# RomeBoardV1_2.net
KiCad netlist of a schematic drawn in EAGLE
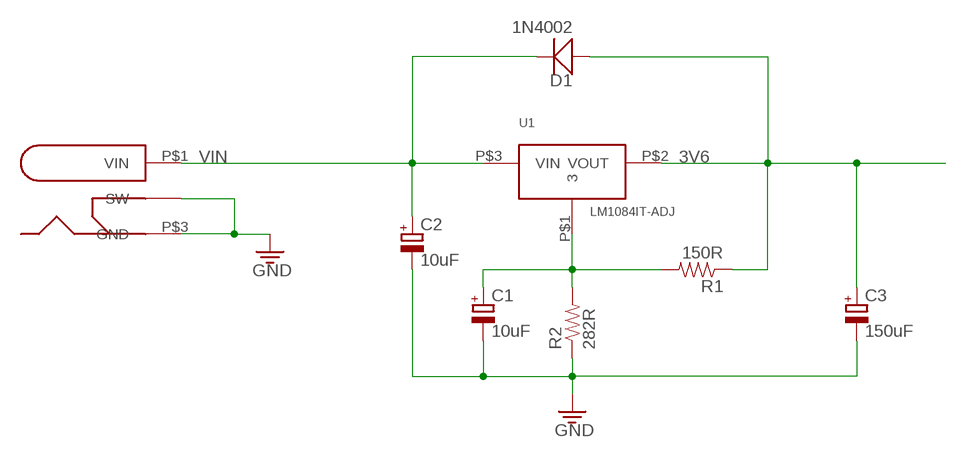
[diagram p0: schematic, sheet 1]
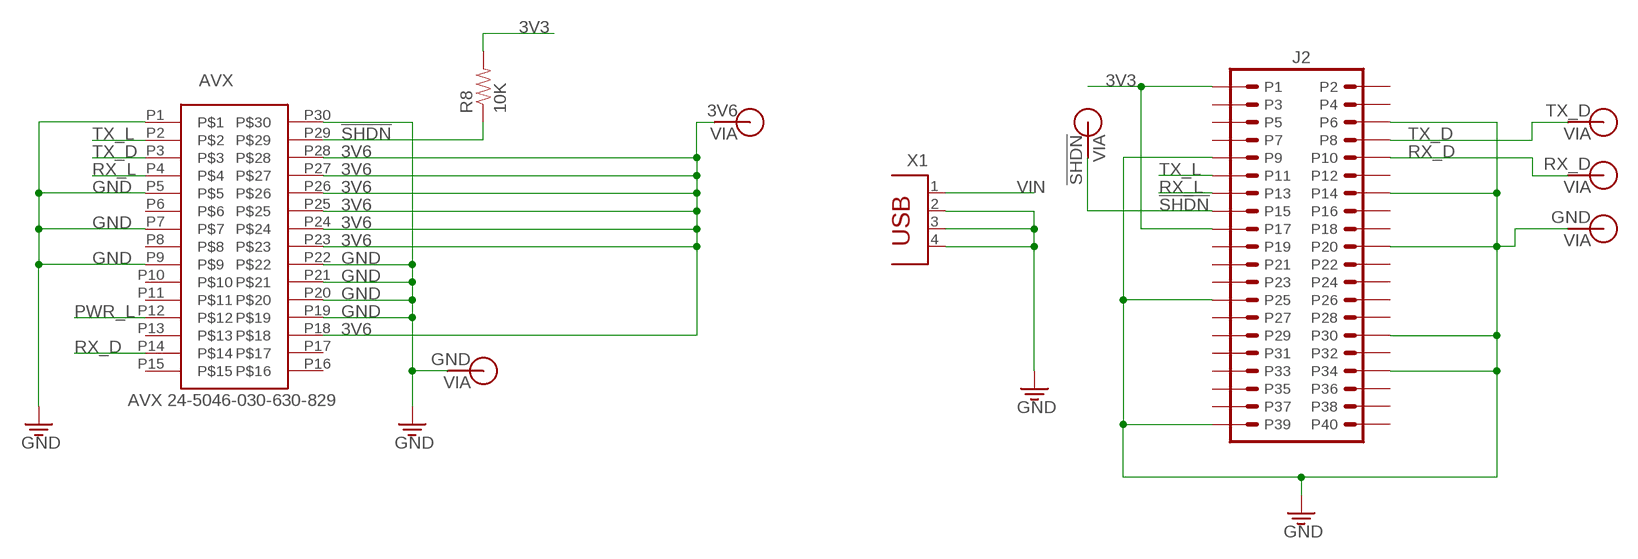
[diagram p1: schematic, sheet 2]
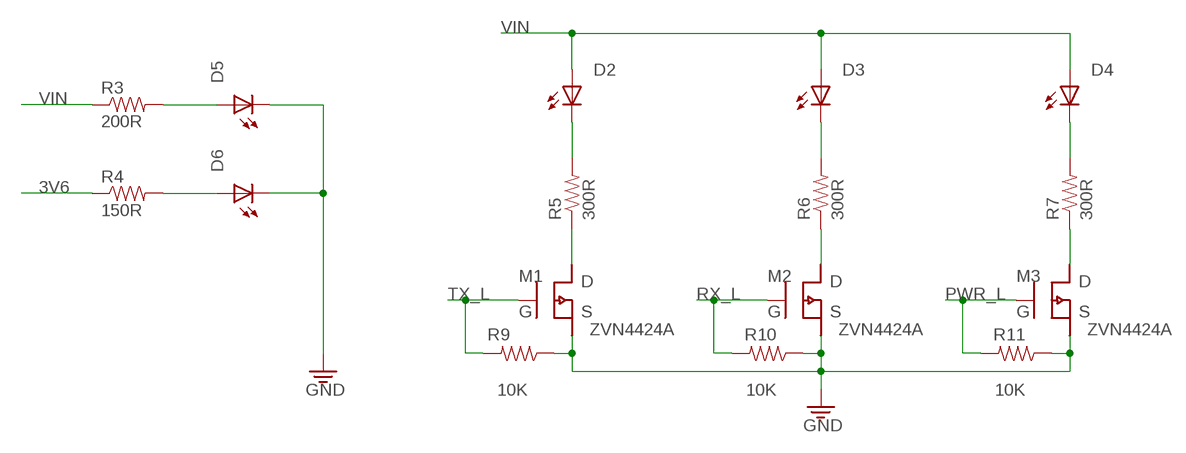
[diagram p2: schematic, sheet 3]
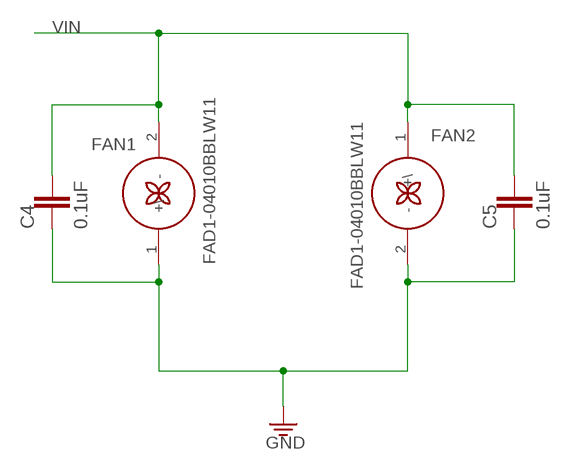
[diagram p3: schematic, sheet 4]

(export (version "E")
  (design (tool "Eeschema 10.0.6"))
  (components
    (comp (ref "C4")
      (value "0.1uF")
      (footprint "eagle-import:C050-025X075")
      (libsource (lib "eagle-import") (part "CAP5MM-THRU-HOLE"))
    )
    (comp (ref "C5")
      (value "0.1uF")
      (footprint "eagle-import:C050-025X075")
      (libsource (lib "eagle-import") (part "CAP5MM-THRU-HOLE"))
    )
    (comp (ref "FAN1")
      (value "FAD1-04010BBLW11")
      (footprint "eagle-import:1X2-POL")
      (libsource (lib "eagle-import") (part "FAD1-04010BBLW11"))
    )
    (comp (ref "FAN2")
      (value "FAD1-04010BBLW11")
      (footprint "eagle-import:1X2-POL")
      (libsource (lib "eagle-import") (part "FAD1-04010BBLW11"))
    )
    (comp (ref "AVX")
      (value "AVX-24-5046-030-630-829")
      (footprint "eagle-import:AVX-24-5046-630-829")
      (libsource (lib "eagle-import") (part "AVX-24-5046-030-630-829"))
    )
    (comp (ref "J2")
      (value "RASPBERRY-PI-HEADER")
      (footprint "eagle-import:HEADER-20X02")
      (libsource (lib "eagle-import") (part "RASPBERRY-PI-HEADER"))
    )
    (comp (ref "R8")
      (value "10K")
      (footprint "eagle-import:AXIAL-0.4")
      (libsource (lib "eagle-import") (part "RESISTOR-PTH0.4"))
    )
    (comp (ref "V1")
      (value "TX_D")
      (footprint "eagle-import:VIA-60MIL")
      (libsource (lib "eagle-import") (part "VIA-60MIL"))
    )
    (comp (ref "V2")
      (value "RX_D")
      (footprint "eagle-import:VIA-60MIL")
      (libsource (lib "eagle-import") (part "VIA-60MIL"))
    )
    (comp (ref "V3")
      (value "GND")
      (footprint "eagle-import:VIA-60MIL")
      (libsource (lib "eagle-import") (part "VIA-60MIL"))
    )
    (comp (ref "V4")
      (value "GND")
      (footprint "eagle-import:VIA-120MIL")
      (libsource (lib "eagle-import") (part "VIA-120MIL"))
    )
    (comp (ref "V5")
      (value "3V6")
      (footprint "eagle-import:VIA-120MIL")
      (libsource (lib "eagle-import") (part "VIA-120MIL"))
    )
    (comp (ref "V6")
      (value "!SHDN")
      (footprint "eagle-import:VIA-60MIL")
      (libsource (lib "eagle-import") (part "VIA-60MIL"))
    )
    (comp (ref "X1")
      (value "PN87520")
      (footprint "eagle-import:PN87520")
      (libsource (lib "eagle-import") (part "PN87520"))
    )
    (comp (ref "D2")
      (value "LEDTHRU-HOLE-CONNECTOR")
      (footprint "eagle-import:1X2-POL")
      (libsource (lib "eagle-import") (part "LEDTHRU-HOLE-CONNECTOR"))
    )
    (comp (ref "D3")
      (value "LEDTHRU-HOLE-CONNECTOR")
      (footprint "eagle-import:1X2-POL")
      (libsource (lib "eagle-import") (part "LEDTHRU-HOLE-CONNECTOR"))
    )
    (comp (ref "D4")
      (value "LEDTHRU-HOLE-CONNECTOR")
      (footprint "eagle-import:1X2-POL")
      (libsource (lib "eagle-import") (part "LEDTHRU-HOLE-CONNECTOR"))
    )
    (comp (ref "D5")
      (value "LEDTHRU-HOLE-CONNECTOR")
      (footprint "eagle-import:1X2-POL")
      (libsource (lib "eagle-import") (part "LEDTHRU-HOLE-CONNECTOR"))
    )
    (comp (ref "D6")
      (value "LEDTHRU-HOLE-CONNECTOR")
      (footprint "eagle-import:1X2-POL")
      (libsource (lib "eagle-import") (part "LEDTHRU-HOLE-CONNECTOR"))
    )
    (comp (ref "M1")
      (value "ZVN4424A")
      (footprint "eagle-import:TO-923-MOS")
      (libsource (lib "eagle-import") (part "ZVN4424A"))
    )
    (comp (ref "M2")
      (value "ZVN4424A")
      (footprint "eagle-import:TO-923-MOS")
      (libsource (lib "eagle-import") (part "ZVN4424A"))
    )
    (comp (ref "M3")
      (value "ZVN4424A")
      (footprint "eagle-import:TO-923-MOS")
      (libsource (lib "eagle-import") (part "ZVN4424A"))
    )
    (comp (ref "R3")
      (value "200R")
      (footprint "eagle-import:AXIAL-0.4")
      (libsource (lib "eagle-import") (part "RESISTOR-PTH0.4"))
    )
    (comp (ref "R4")
      (value "150R")
      (footprint "eagle-import:AXIAL-0.4")
      (libsource (lib "eagle-import") (part "RESISTOR-PTH0.4"))
    )
    (comp (ref "R5")
      (value "300R")
      (footprint "eagle-import:AXIAL-0.4")
      (libsource (lib "eagle-import") (part "RESISTOR-PTH0.4"))
    )
    (comp (ref "R6")
      (value "300R")
      (footprint "eagle-import:AXIAL-0.4")
      (libsource (lib "eagle-import") (part "RESISTOR-PTH0.4"))
    )
    (comp (ref "R7")
      (value "300R")
      (footprint "eagle-import:AXIAL-0.4")
      (libsource (lib "eagle-import") (part "RESISTOR-PTH0.4"))
    )
    (comp (ref "R9")
      (value "10K")
      (footprint "eagle-import:AXIAL-0.4")
      (libsource (lib "eagle-import") (part "RESISTOR-PTH0.4"))
    )
    (comp (ref "R10")
      (value "10K")
      (footprint "eagle-import:AXIAL-0.4")
      (libsource (lib "eagle-import") (part "RESISTOR-PTH0.4"))
    )
    (comp (ref "R11")
      (value "10K")
      (footprint "eagle-import:AXIAL-0.4")
      (libsource (lib "eagle-import") (part "RESISTOR-PTH0.4"))
    )
    (comp (ref "C1")
      (value "10uF")
      (footprint "eagle-import:E2,5-7")
      (libsource (lib "eagle-import") (part "CPOL-EUE2.5-7"))
    )
    (comp (ref "C2")
      (value "10uF")
      (footprint "eagle-import:E2,5-7")
      (libsource (lib "eagle-import") (part "CPOL-EUE2.5-7"))
    )
    (comp (ref "C3")
      (value "150uF")
      (footprint "eagle-import:E5-13")
      (libsource (lib "eagle-import") (part "CPOL-EUE5-13"))
    )
    (comp (ref "D1")
      (value "1N4002")
      (footprint "eagle-import:DO-201AD")
      (libsource (lib "eagle-import") (part "1N4002"))
    )
    (comp (ref "R1")
      (value "150R")
      (footprint "eagle-import:AXIAL-0.4")
      (libsource (lib "eagle-import") (part "RESISTOR-PTH0.4"))
    )
    (comp (ref "R2")
      (value "282R")
      (footprint "eagle-import:AXIAL-0.4")
      (libsource (lib "eagle-import") (part "RESISTOR-PTH0.4"))
    )
    (comp (ref "U$2")
      (value "PJ-002A")
      (footprint "eagle-import:PJ-002A")
      (libsource (lib "eagle-import") (part "PJ-002A"))
    )
    (comp (ref "U1")
      (value "LM1084IT-ADJ")
      (footprint "eagle-import:TO-220-507302B00000G")
      (libsource (lib "eagle-import") (part "LM1084IT-ADJ"))
    )
  )
  (nets
    (net (code "1") (name "3V3") (class "Default")
      (node (ref "J2") (pin "P1") (pinfunction "P1_P1") (pintype "passive"))
      (node (ref "J2") (pin "P17") (pinfunction "P17_P17") (pintype "passive"))
      (node (ref "R8") (pin "2") (pinfunction "2_2") (pintype "passive"))
    )
    (net (code "2") (name "3V6") (class "Default")
      (node (ref "AVX") (pin "P18") (pinfunction "P$18_P18") (pintype "bidirectional"))
      (node (ref "AVX") (pin "P23") (pinfunction "P$23_P23") (pintype "bidirectional"))
      (node (ref "AVX") (pin "P24") (pinfunction "P$24_P24") (pintype "bidirectional"))
      (node (ref "AVX") (pin "P25") (pinfunction "P$25_P25") (pintype "bidirectional"))
      (node (ref "AVX") (pin "P26") (pinfunction "P$26_P26") (pintype "bidirectional"))
      (node (ref "AVX") (pin "P27") (pinfunction "P$27_P27") (pintype "bidirectional"))
      (node (ref "AVX") (pin "P28") (pinfunction "P$28_P28") (pintype "bidirectional"))
      (node (ref "C3") (pin "+") (pinfunction "+_+") (pintype "passive"))
      (node (ref "D1") (pin "P$1") (pinfunction "A_P$1") (pintype "bidirectional"))
      (node (ref "R1") (pin "1") (pinfunction "1_1") (pintype "passive"))
      (node (ref "R4") (pin "1") (pinfunction "1_1") (pintype "passive"))
      (node (ref "U1") (pin "P$2") (pinfunction "VOUT_P$2") (pintype "bidirectional"))
      (node (ref "V5") (pin "P$1") (pinfunction "P$1_P$1") (pintype "bidirectional"))
    )
    (net (code "3") (name "GND") (class "Default")
      (node (ref "AVX") (pin "P1") (pinfunction "P$1_P1") (pintype "bidirectional"))
      (node (ref "AVX") (pin "P19") (pinfunction "P$19_P19") (pintype "bidirectional"))
      (node (ref "AVX") (pin "P20") (pinfunction "P$20_P20") (pintype "bidirectional"))
      (node (ref "AVX") (pin "P21") (pinfunction "P$21_P21") (pintype "bidirectional"))
      (node (ref "AVX") (pin "P22") (pinfunction "P$22_P22") (pintype "bidirectional"))
      (node (ref "AVX") (pin "P30") (pinfunction "P$30_P30") (pintype "bidirectional"))
      (node (ref "AVX") (pin "P5") (pinfunction "P$5_P5") (pintype "bidirectional"))
      (node (ref "AVX") (pin "P7") (pinfunction "P$7_P7") (pintype "bidirectional"))
      (node (ref "AVX") (pin "P9") (pinfunction "P$9_P9") (pintype "bidirectional"))
      (node (ref "C1") (pin "-") (pinfunction "-_-") (pintype "passive"))
      (node (ref "C2") (pin "-") (pinfunction "-_-") (pintype "passive"))
      (node (ref "C3") (pin "-") (pinfunction "-_-") (pintype "passive"))
      (node (ref "C4") (pin "2") (pinfunction "P$2_2") (pintype "passive"))
      (node (ref "C5") (pin "2") (pinfunction "P$2_2") (pintype "passive"))
      (node (ref "D5") (pin "2") (pinfunction "C_2") (pintype "passive"))
      (node (ref "D6") (pin "2") (pinfunction "C_2") (pintype "passive"))
      (node (ref "FAN1") (pin "1") (pinfunction "+\\_1") (pintype "bidirectional"))
      (node (ref "FAN2") (pin "2") (pinfunction "-_2") (pintype "bidirectional"))
      (node (ref "J2") (pin "P14") (pinfunction "P14_P14") (pintype "passive"))
      (node (ref "J2") (pin "P20") (pinfunction "P20_P20") (pintype "passive"))
      (node (ref "J2") (pin "P25") (pinfunction "P25_P25") (pintype "passive"))
      (node (ref "J2") (pin "P30") (pinfunction "P30_P30") (pintype "passive"))
      (node (ref "J2") (pin "P34") (pinfunction "P34_P34") (pintype "passive"))
      (node (ref "J2") (pin "P39") (pinfunction "P39_P39") (pintype "passive"))
      (node (ref "J2") (pin "P6") (pinfunction "P6_P6") (pintype "passive"))
      (node (ref "J2") (pin "P9") (pinfunction "P9_P9") (pintype "passive"))
      (node (ref "M1") (pin "3") (pinfunction "S_3") (pintype "bidirectional"))
      (node (ref "M2") (pin "3") (pinfunction "S_3") (pintype "bidirectional"))
      (node (ref "M3") (pin "3") (pinfunction "S_3") (pintype "bidirectional"))
      (node (ref "R10") (pin "1") (pinfunction "1_1") (pintype "passive"))
      (node (ref "R11") (pin "1") (pinfunction "1_1") (pintype "passive"))
      (node (ref "R2") (pin "1") (pinfunction "1_1") (pintype "passive"))
      (node (ref "R9") (pin "1") (pinfunction "1_1") (pintype "passive"))
      (node (ref "U$2") (pin "P$2") (pinfunction "SW_P$2") (pintype "bidirectional"))
      (node (ref "U$2") (pin "P$3") (pinfunction "GND_P$3") (pintype "bidirectional"))
      (node (ref "V3") (pin "P$1") (pinfunction "P$1_P$1") (pintype "bidirectional"))
      (node (ref "V4") (pin "P$1") (pinfunction "P$1_P$1") (pintype "bidirectional"))
      (node (ref "X1") (pin "2") (pinfunction "2_2") (pintype "passive"))
      (node (ref "X1") (pin "3") (pinfunction "3_3") (pintype "passive"))
      (node (ref "X1") (pin "4") (pinfunction "4_4") (pintype "passive"))
    )
    (net (code "4") (name "Net-(D2-C)") (class "Default")
      (node (ref "D2") (pin "2") (pinfunction "C_2") (pintype "passive"))
      (node (ref "R5") (pin "2") (pinfunction "2_2") (pintype "passive"))
    )
    (net (code "5") (name "Net-(D3-C)") (class "Default")
      (node (ref "D3") (pin "2") (pinfunction "C_2") (pintype "passive"))
      (node (ref "R6") (pin "2") (pinfunction "2_2") (pintype "passive"))
    )
    (net (code "6") (name "Net-(D4-C)") (class "Default")
      (node (ref "D4") (pin "2") (pinfunction "C_2") (pintype "passive"))
      (node (ref "R7") (pin "2") (pinfunction "2_2") (pintype "passive"))
    )
    (net (code "7") (name "Net-(D5-A)") (class "Default")
      (node (ref "D5") (pin "1") (pinfunction "A_1") (pintype "passive"))
      (node (ref "R3") (pin "2") (pinfunction "2_2") (pintype "passive"))
    )
    (net (code "8") (name "Net-(D6-A)") (class "Default")
      (node (ref "D6") (pin "1") (pinfunction "A_1") (pintype "passive"))
      (node (ref "R4") (pin "2") (pinfunction "2_2") (pintype "passive"))
    )
    (net (code "9") (name "Net-(M1-D)") (class "Default")
      (node (ref "M1") (pin "1") (pinfunction "D_1") (pintype "bidirectional"))
      (node (ref "R5") (pin "1") (pinfunction "1_1") (pintype "passive"))
    )
    (net (code "10") (name "Net-(M2-D)") (class "Default")
      (node (ref "M2") (pin "1") (pinfunction "D_1") (pintype "bidirectional"))
      (node (ref "R6") (pin "1") (pinfunction "1_1") (pintype "passive"))
    )
    (net (code "11") (name "Net-(M3-D)") (class "Default")
      (node (ref "M3") (pin "1") (pinfunction "D_1") (pintype "bidirectional"))
      (node (ref "R7") (pin "1") (pinfunction "1_1") (pintype "passive"))
    )
    (net (code "12") (name "Net-(U1-3)") (class "Default")
      (node (ref "C1") (pin "+") (pinfunction "+_+") (pintype "passive"))
      (node (ref "R1") (pin "2") (pinfunction "2_2") (pintype "passive"))
      (node (ref "R2") (pin "2") (pinfunction "2_2") (pintype "passive"))
      (node (ref "U1") (pin "P$1") (pinfunction "3_P$1") (pintype "bidirectional"))
    )
    (net (code "13") (name "PWR_L") (class "Default")
      (node (ref "AVX") (pin "P12") (pinfunction "P$12_P12") (pintype "bidirectional"))
      (node (ref "M3") (pin "2") (pinfunction "G_2") (pintype "bidirectional"))
      (node (ref "R11") (pin "2") (pinfunction "2_2") (pintype "passive"))
    )
    (net (code "14") (name "RX_D") (class "Default")
      (node (ref "AVX") (pin "P14") (pinfunction "P$14_P14") (pintype "bidirectional"))
      (node (ref "J2") (pin "P10") (pinfunction "P10_P10") (pintype "passive"))
      (node (ref "V2") (pin "P$1") (pinfunction "P$1_P$1") (pintype "bidirectional"))
    )
    (net (code "15") (name "RX_L") (class "Default")
      (node (ref "AVX") (pin "P4") (pinfunction "P$4_P4") (pintype "bidirectional"))
      (node (ref "J2") (pin "P13") (pinfunction "P13_P13") (pintype "passive"))
      (node (ref "M2") (pin "2") (pinfunction "G_2") (pintype "bidirectional"))
      (node (ref "R10") (pin "2") (pinfunction "2_2") (pintype "passive"))
    )
    (net (code "16") (name "TX_D") (class "Default")
      (node (ref "AVX") (pin "P3") (pinfunction "P$3_P3") (pintype "bidirectional"))
      (node (ref "J2") (pin "P8") (pinfunction "P8_P8") (pintype "passive"))
      (node (ref "V1") (pin "P$1") (pinfunction "P$1_P$1") (pintype "bidirectional"))
    )
    (net (code "17") (name "TX_L") (class "Default")
      (node (ref "AVX") (pin "P2") (pinfunction "P$2_P2") (pintype "bidirectional"))
      (node (ref "J2") (pin "P11") (pinfunction "P11_P11") (pintype "passive"))
      (node (ref "M1") (pin "2") (pinfunction "G_2") (pintype "bidirectional"))
      (node (ref "R9") (pin "2") (pinfunction "2_2") (pintype "passive"))
    )
    (net (code "18") (name "VIN") (class "Default")
      (node (ref "C2") (pin "+") (pinfunction "+_+") (pintype "passive"))
      (node (ref "C4") (pin "1") (pinfunction "P$1_1") (pintype "passive"))
      (node (ref "C5") (pin "1") (pinfunction "P$1_1") (pintype "passive"))
      (node (ref "D1") (pin "P$2") (pinfunction "C_P$2") (pintype "bidirectional"))
      (node (ref "D2") (pin "1") (pinfunction "A_1") (pintype "passive"))
      (node (ref "D3") (pin "1") (pinfunction "A_1") (pintype "passive"))
      (node (ref "D4") (pin "1") (pinfunction "A_1") (pintype "passive"))
      (node (ref "FAN1") (pin "2") (pinfunction "-_2") (pintype "bidirectional"))
      (node (ref "FAN2") (pin "1") (pinfunction "+\\_1") (pintype "bidirectional"))
      (node (ref "R3") (pin "1") (pinfunction "1_1") (pintype "passive"))
      (node (ref "U$2") (pin "P$1") (pinfunction "VIN_P$1") (pintype "bidirectional"))
      (node (ref "U1") (pin "P$3") (pinfunction "VIN_P$3") (pintype "bidirectional"))
      (node (ref "X1") (pin "1") (pinfunction "1_1") (pintype "passive"))
    )
    (net (code "19") (name "unconnected-(AVX-P$6-PadP6)") (class "Default")
      (node (ref "AVX") (pin "P6") (pinfunction "P$6_P6") (pintype "bidirectional"))
    )
    (net (code "20") (name "unconnected-(AVX-P$8-PadP8)") (class "Default")
      (node (ref "AVX") (pin "P8") (pinfunction "P$8_P8") (pintype "bidirectional"))
    )
    (net (code "21") (name "unconnected-(AVX-P$10-PadP10)") (class "Default")
      (node (ref "AVX") (pin "P10") (pinfunction "P$10_P10") (pintype "bidirectional"))
    )
    (net (code "22") (name "unconnected-(AVX-P$11-PadP11)") (class "Default")
      (node (ref "AVX") (pin "P11") (pinfunction "P$11_P11") (pintype "bidirectional"))
    )
    (net (code "23") (name "unconnected-(AVX-P$13-PadP13)") (class "Default")
      (node (ref "AVX") (pin "P13") (pinfunction "P$13_P13") (pintype "bidirectional"))
    )
    (net (code "24") (name "unconnected-(AVX-P$15-PadP15)") (class "Default")
      (node (ref "AVX") (pin "P15") (pinfunction "P$15_P15") (pintype "bidirectional"))
    )
    (net (code "25") (name "unconnected-(AVX-P$16-PadP16)") (class "Default")
      (node (ref "AVX") (pin "P16") (pinfunction "P$16_P16") (pintype "bidirectional"))
    )
    (net (code "26") (name "unconnected-(AVX-P$17-PadP17)") (class "Default")
      (node (ref "AVX") (pin "P17") (pinfunction "P$17_P17") (pintype "bidirectional"))
    )
    (net (code "27") (name "unconnected-(J2-PadP2)") (class "Default")
      (node (ref "J2") (pin "P2") (pinfunction "P2_P2") (pintype "passive"))
    )
    (net (code "28") (name "unconnected-(J2-PadP3)") (class "Default")
      (node (ref "J2") (pin "P3") (pinfunction "P3_P3") (pintype "passive"))
    )
    (net (code "29") (name "unconnected-(J2-PadP4)") (class "Default")
      (node (ref "J2") (pin "P4") (pinfunction "P4_P4") (pintype "passive"))
    )
    (net (code "30") (name "unconnected-(J2-PadP5)") (class "Default")
      (node (ref "J2") (pin "P5") (pinfunction "P5_P5") (pintype "passive"))
    )
    (net (code "31") (name "unconnected-(J2-PadP7)") (class "Default")
      (node (ref "J2") (pin "P7") (pinfunction "P7_P7") (pintype "passive"))
    )
    (net (code "32") (name "unconnected-(J2-PadP12)") (class "Default")
      (node (ref "J2") (pin "P12") (pinfunction "P12_P12") (pintype "passive"))
    )
    (net (code "33") (name "unconnected-(J2-PadP16)") (class "Default")
      (node (ref "J2") (pin "P16") (pinfunction "P16_P16") (pintype "passive"))
    )
    (net (code "34") (name "unconnected-(J2-PadP18)") (class "Default")
      (node (ref "J2") (pin "P18") (pinfunction "P18_P18") (pintype "passive"))
    )
    (net (code "35") (name "unconnected-(J2-PadP19)") (class "Default")
      (node (ref "J2") (pin "P19") (pinfunction "P19_P19") (pintype "passive"))
    )
    (net (code "36") (name "unconnected-(J2-PadP21)") (class "Default")
      (node (ref "J2") (pin "P21") (pinfunction "P21_P21") (pintype "passive"))
    )
    (net (code "37") (name "unconnected-(J2-PadP22)") (class "Default")
      (node (ref "J2") (pin "P22") (pinfunction "P22_P22") (pintype "passive"))
    )
    (net (code "38") (name "unconnected-(J2-PadP23)") (class "Default")
      (node (ref "J2") (pin "P23") (pinfunction "P23_P23") (pintype "passive"))
    )
    (net (code "39") (name "unconnected-(J2-PadP24)") (class "Default")
      (node (ref "J2") (pin "P24") (pinfunction "P24_P24") (pintype "passive"))
    )
    (net (code "40") (name "unconnected-(J2-PadP26)") (class "Default")
      (node (ref "J2") (pin "P26") (pinfunction "P26_P26") (pintype "passive"))
    )
    (net (code "41") (name "unconnected-(J2-PadP27)") (class "Default")
      (node (ref "J2") (pin "P27") (pinfunction "P27_P27") (pintype "passive"))
    )
    (net (code "42") (name "unconnected-(J2-PadP28)") (class "Default")
      (node (ref "J2") (pin "P28") (pinfunction "P28_P28") (pintype "passive"))
    )
    (net (code "43") (name "unconnected-(J2-PadP29)") (class "Default")
      (node (ref "J2") (pin "P29") (pinfunction "P29_P29") (pintype "passive"))
    )
    (net (code "44") (name "unconnected-(J2-PadP31)") (class "Default")
      (node (ref "J2") (pin "P31") (pinfunction "P31_P31") (pintype "passive"))
    )
    (net (code "45") (name "unconnected-(J2-PadP32)") (class "Default")
      (node (ref "J2") (pin "P32") (pinfunction "P32_P32") (pintype "passive"))
    )
    (net (code "46") (name "unconnected-(J2-PadP33)") (class "Default")
      (node (ref "J2") (pin "P33") (pinfunction "P33_P33") (pintype "passive"))
    )
    (net (code "47") (name "unconnected-(J2-PadP35)") (class "Default")
      (node (ref "J2") (pin "P35") (pinfunction "P35_P35") (pintype "passive"))
    )
    (net (code "48") (name "unconnected-(J2-PadP36)") (class "Default")
      (node (ref "J2") (pin "P36") (pinfunction "P36_P36") (pintype "passive"))
    )
    (net (code "49") (name "unconnected-(J2-PadP37)") (class "Default")
      (node (ref "J2") (pin "P37") (pinfunction "P37_P37") (pintype "passive"))
    )
    (net (code "50") (name "unconnected-(J2-PadP38)") (class "Default")
      (node (ref "J2") (pin "P38") (pinfunction "P38_P38") (pintype "passive"))
    )
    (net (code "51") (name "unconnected-(J2-PadP40)") (class "Default")
      (node (ref "J2") (pin "P40") (pinfunction "P40_P40") (pintype "passive"))
    )
    (net (code "52") (name "~{SHDN}") (class "Default")
      (node (ref "AVX") (pin "P29") (pinfunction "P$29_P29") (pintype "bidirectional"))
      (node (ref "J2") (pin "P15") (pinfunction "P15_P15") (pintype "passive"))
      (node (ref "R8") (pin "1") (pinfunction "1_1") (pintype "passive"))
      (node (ref "V6") (pin "P$1") (pinfunction "P$1_P$1") (pintype "bidirectional"))
    )
  )
)
